# Amplifiers.net
KiCad netlist of a schematic drawn in Altium Designer
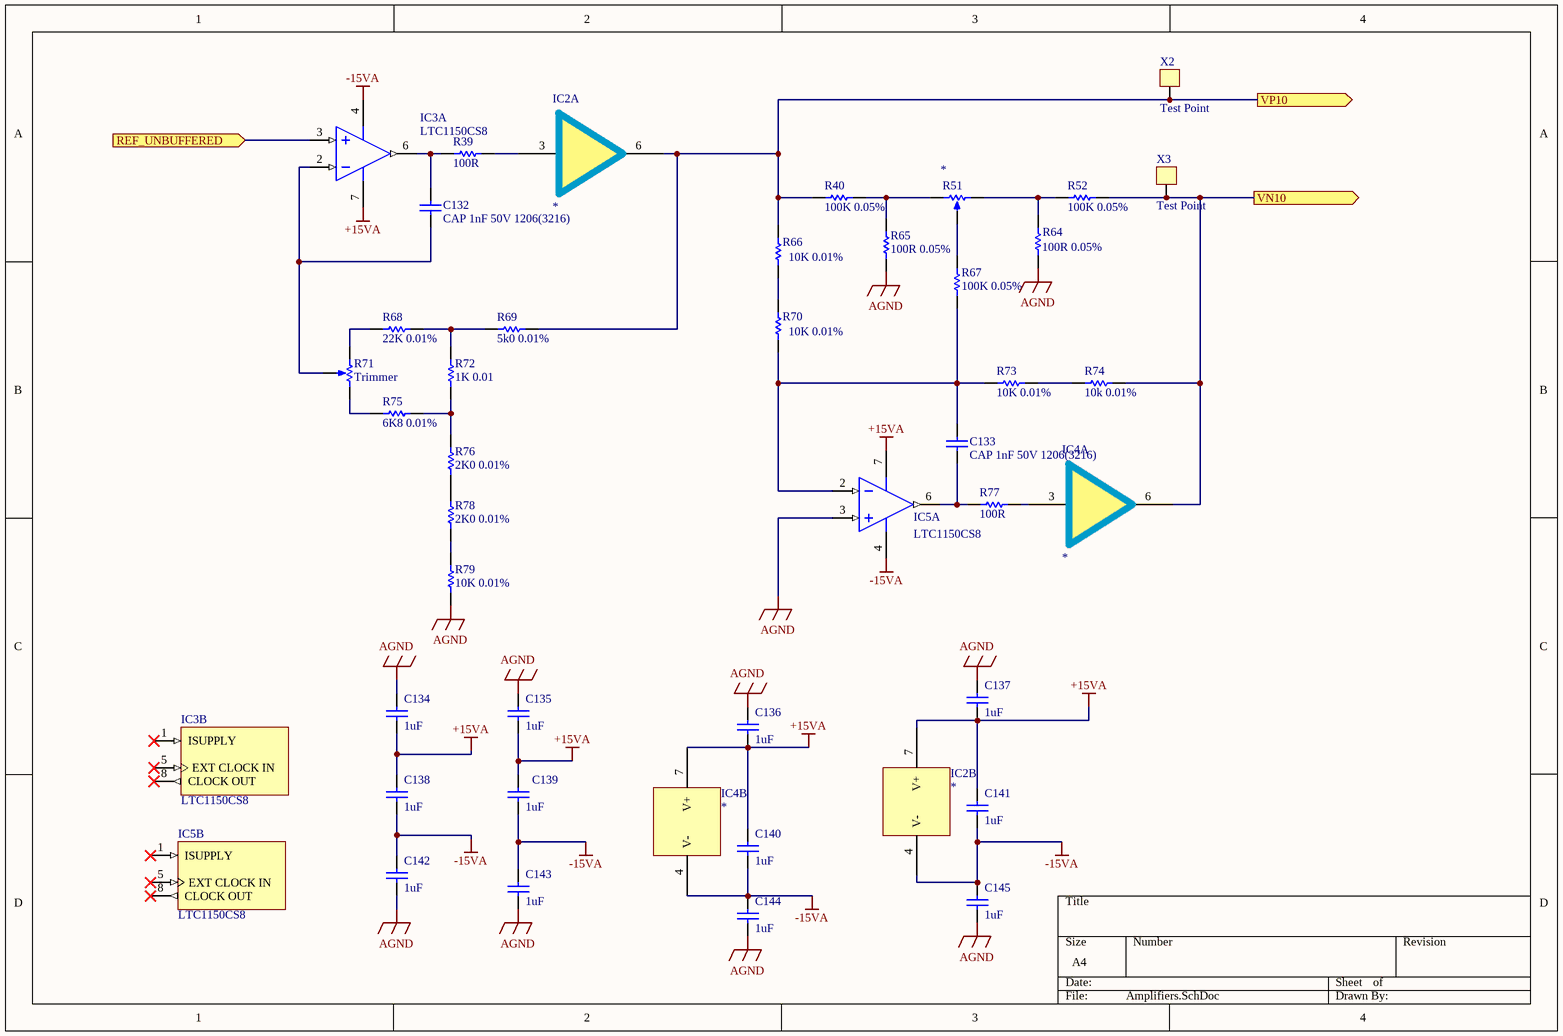
[diagram p0: Amplifiers.SchDoc]

(export (version "E")
  (design (tool "Eeschema 10.0.6"))
  (components
    (comp (ref "C132")
      (value "CAP 1nF 50V 1206(3216)")
      (footprint "CAPC1206(3216)100_N")
      (description "CAP 1nF 50V ±20% 1206 (3216 Metric) Thickness 1mm SMD")
      (fields (field (name "TOLERANCE") "Â±20%"))
      (libsource (lib "Altium Content Vault") (part "CAP"))
    )
    (comp (ref "C133")
      (value "CAP 1nF 50V 1206(3216)")
      (footprint "CAPC1206(3216)100_N")
      (description "CAP 1nF 50V ±20% 1206 (3216 Metric) Thickness 1mm SMD")
      (fields (field (name "TOLERANCE") "Â±20%"))
      (libsource (lib "Altium Content Vault") (part "CAP"))
    )
    (comp (ref "C134")
      (value "1uF")
      (footprint "CAPC1206(3216)110_N")
      (description "CAP 1uF 50V -20% to +80% 1206 (3216 Metric) Thickness 1.05mm SMD")
      (fields (field (name "TOLERANCE") "-20% to +80%") (field (name "Comment") "CAP 1uF 50V 1206(3216)"))
      (libsource (lib "Altium Content Vault") (part "CMP-1037-04724-1"))
    )
    (comp (ref "C135")
      (value "1uF")
      (footprint "CAPC1206(3216)110_N")
      (description "CAP 1uF 50V -20% to +80% 1206 (3216 Metric) Thickness 1.05mm SMD")
      (fields (field (name "TOLERANCE") "-20% to +80%") (field (name "Comment") "CAP 1uF 50V 1206(3216)"))
      (libsource (lib "Altium Content Vault") (part "CMP-1037-04724-1"))
    )
    (comp (ref "C136")
      (value "1uF")
      (footprint "CAPC1206(3216)110_N")
      (description "CAP 1uF 50V -20% to +80% 1206 (3216 Metric) Thickness 1.05mm SMD")
      (fields (field (name "TOLERANCE") "-20% to +80%") (field (name "Comment") "CAP 1uF 50V 1206(3216)"))
      (libsource (lib "Altium Content Vault") (part "CMP-1037-04724-1"))
    )
    (comp (ref "C137")
      (value "1uF")
      (footprint "CAPC1206(3216)110_N")
      (description "CAP 1uF 50V -20% to +80% 1206 (3216 Metric) Thickness 1.05mm SMD")
      (fields (field (name "TOLERANCE") "-20% to +80%") (field (name "Comment") "CAP 1uF 50V 1206(3216)"))
      (libsource (lib "Altium Content Vault") (part "CMP-1037-04724-1"))
    )
    (comp (ref "C138")
      (value "1uF")
      (footprint "CAPC1206(3216)110_N")
      (description "CAP 1uF 50V -20% to +80% 1206 (3216 Metric) Thickness 1.05mm SMD")
      (fields (field (name "TOLERANCE") "-20% to +80%") (field (name "Comment") "CAP 1uF 50V 1206(3216)"))
      (libsource (lib "Altium Content Vault") (part "CMP-1037-04724-1"))
    )
    (comp (ref "C139")
      (value "1uF")
      (footprint "CAPC1206(3216)110_N")
      (description "CAP 1uF 50V -20% to +80% 1206 (3216 Metric) Thickness 1.05mm SMD")
      (fields (field (name "TOLERANCE") "-20% to +80%") (field (name "Comment") "CAP 1uF 50V 1206(3216)"))
      (libsource (lib "Altium Content Vault") (part "CMP-1037-04724-1"))
    )
    (comp (ref "C140")
      (value "1uF")
      (footprint "CAPC1206(3216)110_N")
      (description "CAP 1uF 50V -20% to +80% 1206 (3216 Metric) Thickness 1.05mm SMD")
      (fields (field (name "TOLERANCE") "-20% to +80%") (field (name "Comment") "CAP 1uF 50V 1206(3216)"))
      (libsource (lib "Altium Content Vault") (part "CMP-1037-04724-1"))
    )
    (comp (ref "C141")
      (value "1uF")
      (footprint "CAPC1206(3216)110_N")
      (description "CAP 1uF 50V -20% to +80% 1206 (3216 Metric) Thickness 1.05mm SMD")
      (fields (field (name "TOLERANCE") "-20% to +80%") (field (name "Comment") "CAP 1uF 50V 1206(3216)"))
      (libsource (lib "Altium Content Vault") (part "CMP-1037-04724-1"))
    )
    (comp (ref "C142")
      (value "1uF")
      (footprint "CAPC1206(3216)110_N")
      (description "CAP 1uF 50V -20% to +80% 1206 (3216 Metric) Thickness 1.05mm SMD")
      (fields (field (name "TOLERANCE") "-20% to +80%") (field (name "Comment") "CAP 1uF 50V 1206(3216)"))
      (libsource (lib "Altium Content Vault") (part "CMP-1037-04724-1"))
    )
    (comp (ref "C143")
      (value "1uF")
      (footprint "CAPC1206(3216)110_N")
      (description "CAP 1uF 50V -20% to +80% 1206 (3216 Metric) Thickness 1.05mm SMD")
      (fields (field (name "TOLERANCE") "-20% to +80%") (field (name "Comment") "CAP 1uF 50V 1206(3216)"))
      (libsource (lib "Altium Content Vault") (part "CMP-1037-04724-1"))
    )
    (comp (ref "C144")
      (value "1uF")
      (footprint "CAPC1206(3216)110_N")
      (description "CAP 1uF 50V -20% to +80% 1206 (3216 Metric) Thickness 1.05mm SMD")
      (fields (field (name "TOLERANCE") "-20% to +80%") (field (name "Comment") "CAP 1uF 50V 1206(3216)"))
      (libsource (lib "Altium Content Vault") (part "CMP-1037-04724-1"))
    )
    (comp (ref "C145")
      (value "1uF")
      (footprint "CAPC1206(3216)110_N")
      (description "CAP 1uF 50V -20% to +80% 1206 (3216 Metric) Thickness 1.05mm SMD")
      (fields (field (name "TOLERANCE") "-20% to +80%") (field (name "Comment") "CAP 1uF 50V 1206(3216)"))
      (libsource (lib "Altium Content Vault") (part "CMP-1037-04724-1"))
    )
    (comp (ref "IC2") (value "*") (footprint "SO8_L") (libsource (lib "CurrentSource") (part "BUF634")))
    (comp (ref "IC3")
      (value "LTC1150CS8")
      (footprint "LT-S8-8_M")
      (fields
        (field (name "MANUFACTURER") "Linear Technology")
        (field (name "LINEAR TECHNOLOGY PART NUMBER") "LTC1150")
      )
      (libsource (lib "") (part "LT-LTC1150-S8-8_1"))
    )
    (comp (ref "IC4") (value "*") (footprint "SO8_L") (libsource (lib "CurrentSource") (part "BUF634")))
    (comp (ref "IC5")
      (value "LTC1150CS8")
      (footprint "LT-S8-8_M")
      (fields
        (field (name "MANUFACTURER") "Linear Technology")
        (field (name "LINEAR TECHNOLOGY PART NUMBER") "LTC1150")
      )
      (libsource (lib "") (part "LT-LTC1150-S8-8_1"))
    )
    (comp (ref "R39")
      (value "100R")
      (footprint "RESC0805(2012)_N")
      (description "1M 0.125W 1% 0805 (2012 Metric)  SMD")
      (fields (field (name "POWER") "0.125 W") (field (name "TOLERANCE") "1 %"))
      (libsource (lib "Altium Content Vault") (part "CMP-1013-00849-1"))
    )
    (comp (ref "R40")
      (value "100K 0.05%")
      (footprint "RESC0805(2012)_N")
      (description "1M 0.125W 1% 0805 (2012 Metric)  SMD")
      (fields (field (name "POWER") "0.125 W") (field (name "TOLERANCE") "1 %"))
      (libsource (lib "Altium Content Vault") (part "CMP-1013-00849-1"))
    )
    (comp (ref "R51")
      (value "*")
      (footprint "TrimPot")
      (libsource (lib "CurrentSource") (part "Vishay Trimmer"))
    )
    (comp (ref "R52")
      (value "100K 0.05%")
      (footprint "RESC0805(2012)_N")
      (description "1M 0.125W 1% 0805 (2012 Metric)  SMD")
      (fields (field (name "POWER") "0.125 W") (field (name "TOLERANCE") "1 %"))
      (libsource (lib "Altium Content Vault") (part "CMP-1013-00849-1"))
    )
    (comp (ref "R64")
      (value "100R 0.05%")
      (footprint "RESC0805(2012)_N")
      (description "1M 0.125W 1% 0805 (2012 Metric)  SMD")
      (fields (field (name "POWER") "0.125 W") (field (name "TOLERANCE") "1 %"))
      (libsource (lib "Altium Content Vault") (part "CMP-1013-00849-1"))
    )
    (comp (ref "R65")
      (value "100R 0.05%")
      (footprint "RESC0805(2012)_N")
      (description "1M 0.125W 1% 0805 (2012 Metric)  SMD")
      (fields (field (name "POWER") "0.125 W") (field (name "TOLERANCE") "1 %"))
      (libsource (lib "Altium Content Vault") (part "CMP-1013-00849-1"))
    )
    (comp (ref "R66")
      (value "10K 0.01%")
      (footprint "RESC3116X65X40LL10T20")
      (fields (field (name "MANUFACTURER") "Yageo") (field (name "PART NUMBER") "RC1206FR-0710K2L"))
      (libsource (lib "Altium Content Vault") (part "CMP-2003-03538-1"))
    )
    (comp (ref "R67")
      (value "100K 0.05%")
      (footprint "RESC0805(2012)_N")
      (description "1M 0.125W 1% 0805 (2012 Metric)  SMD")
      (fields (field (name "POWER") "0.125 W") (field (name "TOLERANCE") "1 %"))
      (libsource (lib "Altium Content Vault") (part "CMP-1013-00849-1"))
    )
    (comp (ref "R68")
      (value "22K 0.01%")
      (footprint "RESC0805(2012)_N")
      (description "1M 0.125W 1% 0805 (2012 Metric)  SMD")
      (fields (field (name "POWER") "0.125 W") (field (name "TOLERANCE") "1 %"))
      (libsource (lib "Altium Content Vault") (part "CMP-1013-00849-1"))
    )
    (comp (ref "R69")
      (value "5k0 0.01%")
      (footprint "RESC0805(2012)_N")
      (description "1M 0.125W 1% 0805 (2012 Metric)  SMD")
      (fields (field (name "POWER") "0.125 W") (field (name "TOLERANCE") "1 %"))
      (libsource (lib "Altium Content Vault") (part "CMP-1013-00849-1"))
    )
    (comp (ref "R70")
      (value "10K 0.01%")
      (footprint "RESC3116X65X40LL10T20")
      (fields (field (name "MANUFACTURER") "Yageo") (field (name "PART NUMBER") "RC1206FR-0710K2L"))
      (libsource (lib "Altium Content Vault") (part "CMP-2003-03538-1"))
    )
    (comp (ref "R71")
      (value "Trimmer")
      (footprint "TrimPot")
      (libsource (lib "CurrentSource") (part "Vishay Trimmer"))
    )
    (comp (ref "R72")
      (value "1K 0.01")
      (footprint "RESC3116X65X40LL10T20")
      (fields (field (name "MANUFACTURER") "Yageo") (field (name "PART NUMBER") "RC1206FR-0710K2L"))
      (libsource (lib "Altium Content Vault") (part "RES"))
    )
    (comp (ref "R73")
      (value "10K 0.01%")
      (footprint "RESC3116X65X40LL10T20")
      (fields (field (name "MANUFACTURER") "Yageo") (field (name "PART NUMBER") "RC1206FR-0710K2L"))
      (libsource (lib "Altium Content Vault") (part "CMP-2003-03538-1"))
    )
    (comp (ref "R74")
      (value "10k 0.01%")
      (footprint "RESC3116X65X40LL10T20")
      (fields (field (name "MANUFACTURER") "Yageo") (field (name "PART NUMBER") "RC1206FR-0710K2L"))
      (libsource (lib "Altium Content Vault") (part "CMP-2003-03538-1"))
    )
    (comp (ref "R75")
      (value "6K8 0.01%")
      (footprint "RESC0805(2012)_N")
      (description "1M 0.125W 1% 0805 (2012 Metric)  SMD")
      (fields (field (name "POWER") "0.125 W") (field (name "TOLERANCE") "1 %"))
      (libsource (lib "Altium Content Vault") (part "CMP-1013-00849-1"))
    )
    (comp (ref "R76")
      (value "2K0 0.01%")
      (footprint "RESC0805(2012)_N")
      (description "1M 0.125W 1% 0805 (2012 Metric)  SMD")
      (fields (field (name "POWER") "0.125 W") (field (name "TOLERANCE") "1 %"))
      (libsource (lib "Altium Content Vault") (part "CMP-1013-00849-1"))
    )
    (comp (ref "R77")
      (value "100R")
      (footprint "RESC0805(2012)_N")
      (description "1M 0.125W 1% 0805 (2012 Metric)  SMD")
      (fields (field (name "POWER") "0.125 W") (field (name "TOLERANCE") "1 %"))
      (libsource (lib "Altium Content Vault") (part "CMP-1013-00849-1"))
    )
    (comp (ref "R78")
      (value "2K0 0.01%")
      (footprint "RESC0805(2012)_N")
      (description "1M 0.125W 1% 0805 (2012 Metric)  SMD")
      (fields (field (name "POWER") "0.125 W") (field (name "TOLERANCE") "1 %"))
      (libsource (lib "Altium Content Vault") (part "CMP-1013-00849-1"))
    )
    (comp (ref "R79")
      (value "10K 0.01%")
      (footprint "RESC3116X65X40LL10T20")
      (fields (field (name "MANUFACTURER") "Yageo") (field (name "PART NUMBER") "RC1206FR-0710K2L"))
      (libsource (lib "Altium Content Vault") (part "CMP-2003-03538-1"))
    )
    (comp (ref "X2")
      (value "Test Point")
      (footprint "Test Point")
      (libsource (lib "CurrentSource") (part "Test Point"))
    )
    (comp (ref "X3")
      (value "Test Point")
      (footprint "Test Point")
      (libsource (lib "CurrentSource") (part "Test Point"))
    )
  )
  (nets
    (net (code "1") (name "+15VA") (class "Default")
      (node (ref "C134") (pin "1") (pinfunction "1_1") (pintype "passive"))
      (node (ref "C135") (pin "1") (pinfunction "1_1") (pintype "passive"))
      (node (ref "C136") (pin "1") (pinfunction "1_1") (pintype "passive"))
      (node (ref "C137") (pin "1") (pinfunction "1_1") (pintype "passive"))
      (node (ref "C138") (pin "2") (pinfunction "2_2") (pintype "passive"))
      (node (ref "C139") (pin "2") (pinfunction "2_2") (pintype "passive"))
      (node (ref "C140") (pin "2") (pinfunction "2_2") (pintype "passive"))
      (node (ref "C141") (pin "2") (pinfunction "2_2") (pintype "passive"))
      (node (ref "IC2") (pin "7") (pinfunction "V+_7") (pintype "passive"))
      (node (ref "IC3") (pin "7") (pinfunction "V+_7") (pintype "power_in"))
      (node (ref "IC4") (pin "7") (pinfunction "V+_7") (pintype "passive"))
      (node (ref "IC5") (pin "7") (pinfunction "V+_7") (pintype "power_in"))
    )
    (net (code "2") (name "-15VA") (class "Default")
      (node (ref "C138") (pin "1") (pinfunction "1_1") (pintype "passive"))
      (node (ref "C139") (pin "1") (pinfunction "1_1") (pintype "passive"))
      (node (ref "C140") (pin "1") (pinfunction "1_1") (pintype "passive"))
      (node (ref "C141") (pin "1") (pinfunction "1_1") (pintype "passive"))
      (node (ref "C142") (pin "2") (pinfunction "2_2") (pintype "passive"))
      (node (ref "C143") (pin "2") (pinfunction "2_2") (pintype "passive"))
      (node (ref "C144") (pin "2") (pinfunction "2_2") (pintype "passive"))
      (node (ref "C145") (pin "2") (pinfunction "2_2") (pintype "passive"))
      (node (ref "IC2") (pin "4") (pinfunction "V-_4") (pintype "passive"))
      (node (ref "IC3") (pin "4") (pinfunction "V-_4") (pintype "power_in"))
      (node (ref "IC4") (pin "4") (pinfunction "V-_4") (pintype "passive"))
      (node (ref "IC5") (pin "4") (pinfunction "V-_4") (pintype "power_in"))
    )
    (net (code "3") (name "/REF_UNBUFFERED") (class "Default")
      (node (ref "IC3") (pin "3") (pinfunction "+IN_3") (pintype "input"))
    )
    (net (code "4") (name "/VN10") (class "Default")
      (node (ref "IC4") (pin "6") (pinfunction "Out_6") (pintype "passive"))
      (node (ref "R52") (pin "2") (pinfunction "2_2") (pintype "passive"))
      (node (ref "R74") (pin "1") (pinfunction "1_1") (pintype "passive"))
      (node (ref "X3") (pin "1") (pinfunction "1_1") (pintype "passive"))
    )
    (net (code "5") (name "/VP10") (class "Default")
      (node (ref "IC2") (pin "6") (pinfunction "Out_6") (pintype "passive"))
      (node (ref "R40") (pin "1") (pinfunction "1_1") (pintype "passive"))
      (node (ref "R66") (pin "2") (pinfunction "2_2") (pintype "passive"))
      (node (ref "R69") (pin "2") (pinfunction "2_2") (pintype "passive"))
      (node (ref "X2") (pin "1") (pinfunction "1_1") (pintype "passive"))
    )
    (net (code "6") (name "AGND") (class "Default")
      (node (ref "C134") (pin "2") (pinfunction "2_2") (pintype "passive"))
      (node (ref "C135") (pin "2") (pinfunction "2_2") (pintype "passive"))
      (node (ref "C136") (pin "2") (pinfunction "2_2") (pintype "passive"))
      (node (ref "C137") (pin "2") (pinfunction "2_2") (pintype "passive"))
      (node (ref "C142") (pin "1") (pinfunction "1_1") (pintype "passive"))
      (node (ref "C143") (pin "1") (pinfunction "1_1") (pintype "passive"))
      (node (ref "C144") (pin "1") (pinfunction "1_1") (pintype "passive"))
      (node (ref "C145") (pin "1") (pinfunction "1_1") (pintype "passive"))
      (node (ref "IC5") (pin "3") (pinfunction "+IN_3") (pintype "input"))
      (node (ref "R64") (pin "2") (pinfunction "2_2") (pintype "passive"))
      (node (ref "R65") (pin "2") (pinfunction "2_2") (pintype "passive"))
      (node (ref "R79") (pin "1") (pinfunction "1_1") (pintype "passive"))
    )
    (net (code "7") (name "Net-(IC2A-In)") (class "Default")
      (node (ref "IC2") (pin "3") (pinfunction "In_3") (pintype "passive"))
      (node (ref "R39") (pin "2") (pinfunction "2_2") (pintype "passive"))
    )
    (net (code "8") (name "Net-(IC3A--IN)") (class "Default")
      (node (ref "C132") (pin "2") (pinfunction "2_2") (pintype "passive"))
      (node (ref "IC3") (pin "2") (pinfunction "-IN_2") (pintype "input"))
      (node (ref "R71") (pin "3") (pinfunction "TAP_3") (pintype "passive"))
    )
    (net (code "9") (name "Net-(IC3A-OUT)") (class "Default")
      (node (ref "C132") (pin "1") (pinfunction "1_1") (pintype "passive"))
      (node (ref "IC3") (pin "6") (pinfunction "OUT_6") (pintype "output"))
      (node (ref "R39") (pin "1") (pinfunction "1_1") (pintype "passive"))
    )
    (net (code "10") (name "Net-(IC4A-In)") (class "Default")
      (node (ref "IC4") (pin "3") (pinfunction "In_3") (pintype "passive"))
      (node (ref "R77") (pin "2") (pinfunction "2_2") (pintype "passive"))
    )
    (net (code "11") (name "Net-(IC5A--IN)") (class "Default")
      (node (ref "C133") (pin "1") (pinfunction "1_1") (pintype "passive"))
      (node (ref "IC5") (pin "2") (pinfunction "-IN_2") (pintype "input"))
      (node (ref "R67") (pin "1") (pinfunction "1_1") (pintype "passive"))
      (node (ref "R70") (pin "1") (pinfunction "1_1") (pintype "passive"))
      (node (ref "R73") (pin "2") (pinfunction "2_2") (pintype "passive"))
    )
    (net (code "12") (name "Net-(IC5A-OUT)") (class "Default")
      (node (ref "C133") (pin "2") (pinfunction "2_2") (pintype "passive"))
      (node (ref "IC5") (pin "6") (pinfunction "OUT_6") (pintype "output"))
      (node (ref "R77") (pin "1") (pinfunction "1_1") (pintype "passive"))
    )
    (net (code "13") (name "Net-(R51-BOT)") (class "Default")
      (node (ref "R51") (pin "2") (pinfunction "BOT_2") (pintype "passive"))
      (node (ref "R52") (pin "1") (pinfunction "1_1") (pintype "passive"))
      (node (ref "R64") (pin "1") (pinfunction "1_1") (pintype "passive"))
    )
    (net (code "14") (name "Net-(R51-TAP)") (class "Default")
      (node (ref "R51") (pin "3") (pinfunction "TAP_3") (pintype "passive"))
      (node (ref "R67") (pin "2") (pinfunction "2_2") (pintype "passive"))
    )
    (net (code "15") (name "Net-(R51-TOP)") (class "Default")
      (node (ref "R40") (pin "2") (pinfunction "2_2") (pintype "passive"))
      (node (ref "R51") (pin "1") (pinfunction "TOP_1") (pintype "passive"))
      (node (ref "R65") (pin "1") (pinfunction "1_1") (pintype "passive"))
    )
    (net (code "16") (name "Net-(R66-Pad1)") (class "Default")
      (node (ref "R66") (pin "1") (pinfunction "1_1") (pintype "passive"))
      (node (ref "R70") (pin "2") (pinfunction "2_2") (pintype "passive"))
    )
    (net (code "17") (name "Net-(R68-Pad2)") (class "Default")
      (node (ref "R68") (pin "2") (pinfunction "2_2") (pintype "passive"))
      (node (ref "R69") (pin "1") (pinfunction "1_1") (pintype "passive"))
      (node (ref "R72") (pin "2") (pinfunction "2_2") (pintype "passive"))
    )
    (net (code "18") (name "Net-(R71-BOT)") (class "Default")
      (node (ref "R71") (pin "2") (pinfunction "BOT_2") (pintype "passive"))
      (node (ref "R75") (pin "1") (pinfunction "1_1") (pintype "passive"))
    )
    (net (code "19") (name "Net-(R71-TOP)") (class "Default")
      (node (ref "R68") (pin "1") (pinfunction "1_1") (pintype "passive"))
      (node (ref "R71") (pin "1") (pinfunction "TOP_1") (pintype "passive"))
    )
    (net (code "20") (name "Net-(R72-Pad1)") (class "Default")
      (node (ref "R72") (pin "1") (pinfunction "1_1") (pintype "passive"))
      (node (ref "R75") (pin "2") (pinfunction "2_2") (pintype "passive"))
      (node (ref "R76") (pin "2") (pinfunction "2_2") (pintype "passive"))
    )
    (net (code "21") (name "Net-(R73-Pad1)") (class "Default")
      (node (ref "R73") (pin "1") (pinfunction "1_1") (pintype "passive"))
      (node (ref "R74") (pin "2") (pinfunction "2_2") (pintype "passive"))
    )
    (net (code "22") (name "Net-(R76-Pad1)") (class "Default")
      (node (ref "R76") (pin "1") (pinfunction "1_1") (pintype "passive"))
      (node (ref "R78") (pin "2") (pinfunction "2_2") (pintype "passive"))
    )
    (net (code "23") (name "Net-(R78-Pad1)") (class "Default")
      (node (ref "R78") (pin "1") (pinfunction "1_1") (pintype "passive"))
      (node (ref "R79") (pin "2") (pinfunction "2_2") (pintype "passive"))
    )
    (net (code "24") (name "unconnected-(IC3B-CLOCK_OUT-Pad8)") (class "Default")
      (node (ref "IC3") (pin "8") (pinfunction "CLOCK_OUT_8") (pintype "output+no_connect"))
    )
    (net (code "25") (name "unconnected-(IC3B-EXT_CLOCK_IN-Pad5)") (class "Default")
      (node (ref "IC3") (pin "5") (pinfunction "EXT_CLOCK_IN_5") (pintype "input+no_connect"))
    )
    (net (code "26") (name "unconnected-(IC3B-ISUPPLY-Pad1)") (class "Default")
      (node (ref "IC3") (pin "1") (pinfunction "ISUPPLY_1") (pintype "input+no_connect"))
    )
    (net (code "27") (name "unconnected-(IC5B-CLOCK_OUT-Pad8)") (class "Default")
      (node (ref "IC5") (pin "8") (pinfunction "CLOCK_OUT_8") (pintype "output+no_connect"))
    )
    (net (code "28") (name "unconnected-(IC5B-EXT_CLOCK_IN-Pad5)") (class "Default")
      (node (ref "IC5") (pin "5") (pinfunction "EXT_CLOCK_IN_5") (pintype "input+no_connect"))
    )
    (net (code "29") (name "unconnected-(IC5B-ISUPPLY-Pad1)") (class "Default")
      (node (ref "IC5") (pin "1") (pinfunction "ISUPPLY_1") (pintype "input+no_connect"))
    )
  )
)
